# xaef_V0.net
KiCad netlist of a schematic drawn in EAGLE
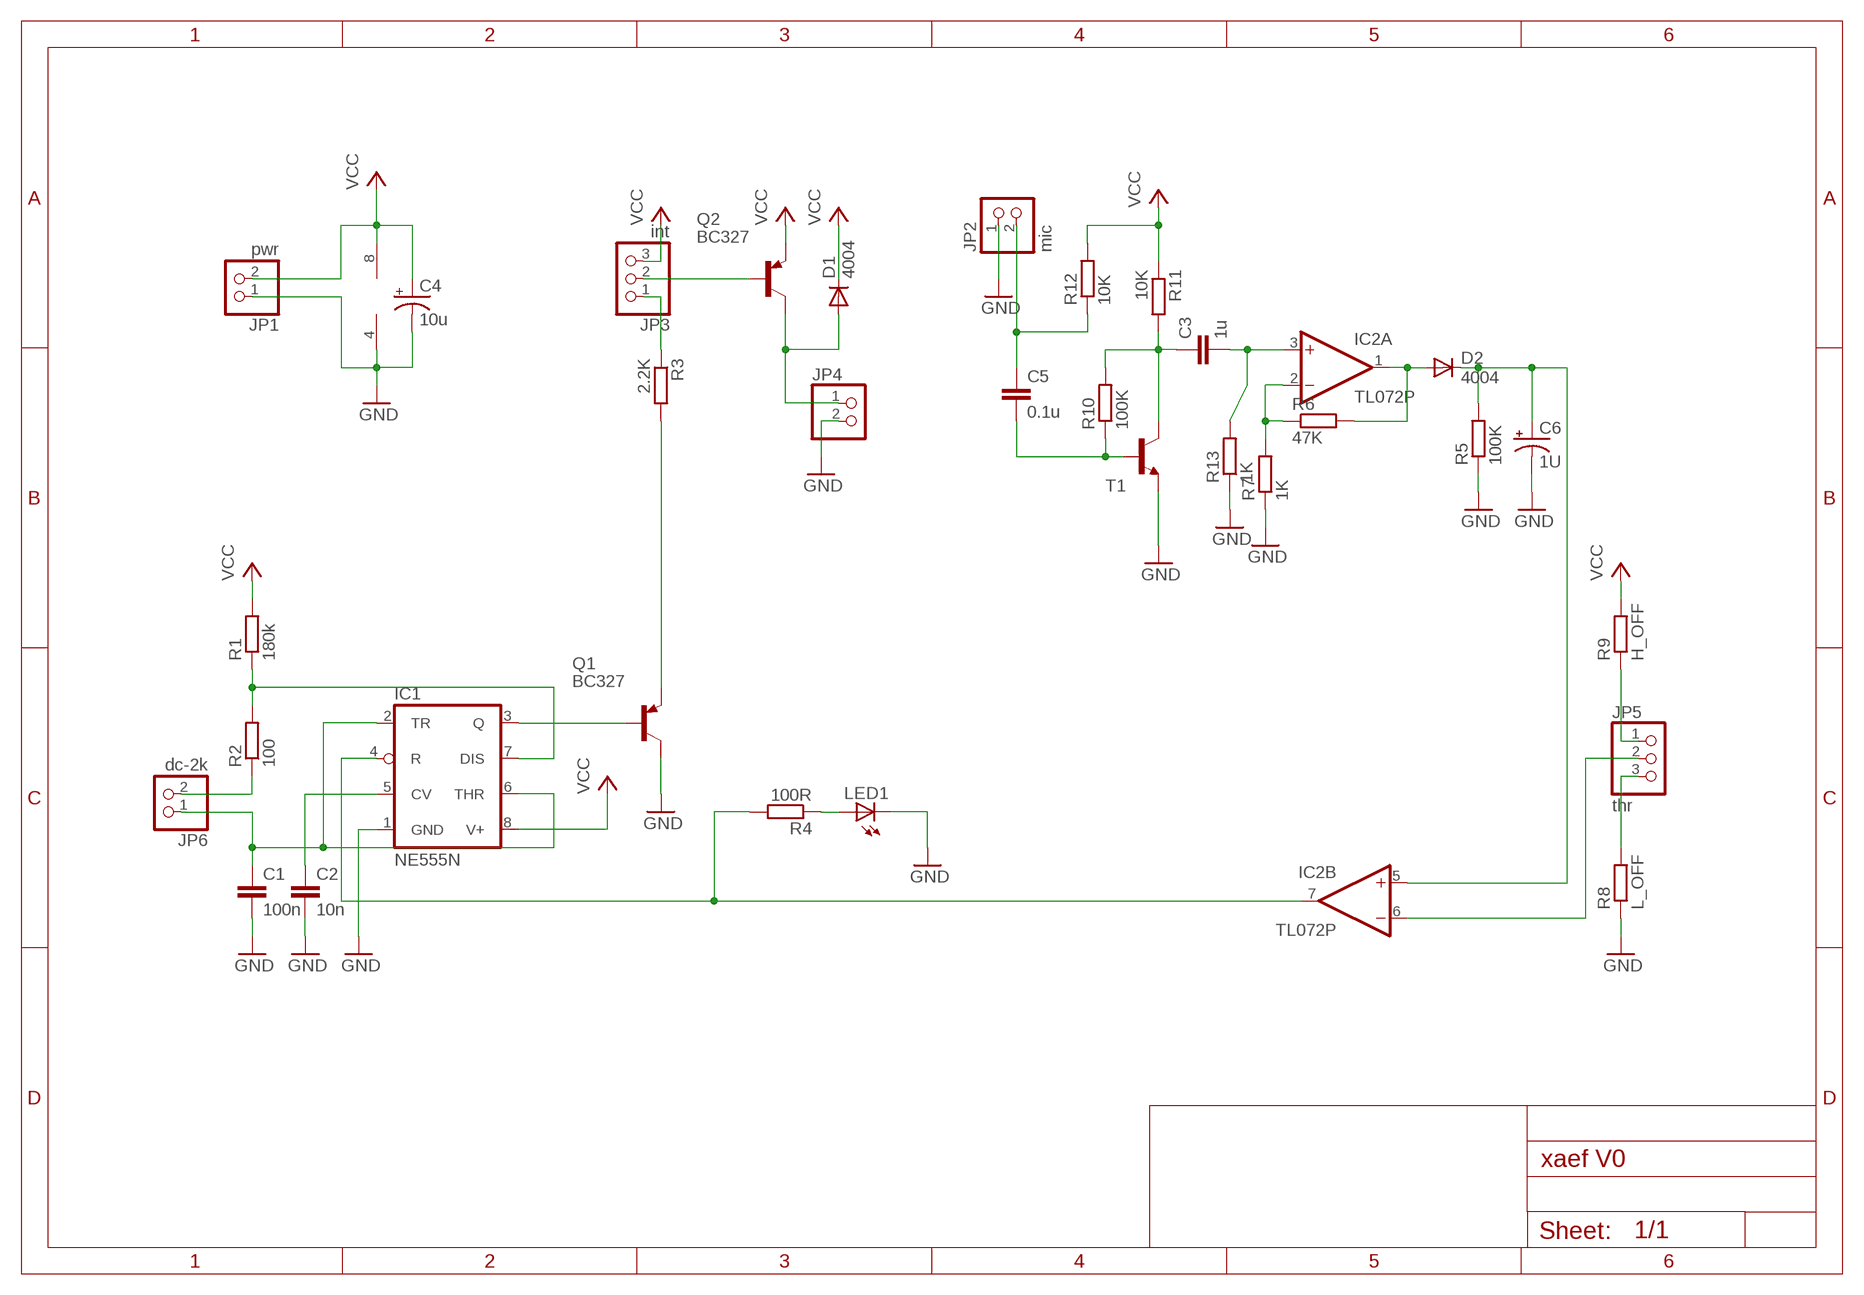
[diagram p0: schematic, sheet 1]

(export (version "E")
  (design (tool "Eeschema 10.0.6"))
  (components
    (comp (ref "C1")
      (value "100n")
      (footprint "eagle-import:C050-030X075")
      (libsource (lib "eagle-import") (part "resistor_C-EU050-030X075"))
    )
    (comp (ref "C2")
      (value "10n")
      (footprint "eagle-import:C050-030X075")
      (libsource (lib "eagle-import") (part "resistor_C-EU050-030X075"))
    )
    (comp (ref "C3")
      (value "1u")
      (footprint "eagle-import:C050-030X075")
      (libsource (lib "eagle-import") (part "resistor_C-EU050-030X075"))
    )
    (comp (ref "C4")
      (value "10u")
      (footprint "eagle-import:E3,5-8")
      (libsource (lib "eagle-import") (part "CPOL-USE3.5-8"))
    )
    (comp (ref "C5")
      (value "0.1u")
      (footprint "eagle-import:C050-025X075")
      (libsource (lib "eagle-import") (part "C-EU050-025X075"))
    )
    (comp (ref "C6")
      (value "1U")
      (footprint "eagle-import:E3,5-8")
      (libsource (lib "eagle-import") (part "CPOL-USE3.5-8"))
    )
    (comp (ref "D1")
      (value "4004")
      (footprint "eagle-import:D-2.5")
      (libsource (lib "eagle-import") (part "DIODE-D-2.5"))
    )
    (comp (ref "D2")
      (value "4004")
      (footprint "eagle-import:D-2.5")
      (libsource (lib "eagle-import") (part "DIODE-D-2.5"))
    )
    (comp (ref "IC1")
      (value "NE555N")
      (footprint "eagle-import:DIL08-ROUND")
      (libsource (lib "eagle-import") (part "555NNE"))
    )
    (comp (ref "IC2")
      (value "TL072P")
      (footprint "eagle-import:DIL08")
      (libsource (lib "eagle-import") (part "TL072P"))
    )
    (comp (ref "JP1")
      (value "pwr")
      (footprint "eagle-import:1X02")
      (libsource (lib "eagle-import") (part "PINHD-1X2"))
    )
    (comp (ref "JP2")
      (value "mic")
      (footprint "eagle-import:1X02")
      (libsource (lib "eagle-import") (part "PINHD-1X2"))
    )
    (comp (ref "JP3")
      (value "int")
      (footprint "eagle-import:1X03")
      (libsource (lib "eagle-import") (part "PINHD-1X3"))
    )
    (comp (ref "JP4")
      (value "PINHD-1X2")
      (footprint "eagle-import:1X02")
      (libsource (lib "eagle-import") (part "PINHD-1X2"))
    )
    (comp (ref "JP5")
      (value "thr")
      (footprint "eagle-import:1X03")
      (libsource (lib "eagle-import") (part "PINHD-1X3"))
    )
    (comp (ref "JP6")
      (value "dc-2k")
      (footprint "eagle-import:1X02")
      (libsource (lib "eagle-import") (part "PINHD-1X2"))
    )
    (comp (ref "LED1")
      (value "LED5MM")
      (footprint "eagle-import:LED5MM")
      (libsource (lib "eagle-import") (part "LED5MM"))
    )
    (comp (ref "Q1")
      (value "BC327")
      (footprint "eagle-import:TO92-EBC")
      (libsource (lib "eagle-import") (part "BC327-25"))
    )
    (comp (ref "Q2")
      (value "BC327")
      (footprint "eagle-import:TO92-EBC")
      (libsource (lib "eagle-import") (part "BC327-25"))
    )
    (comp (ref "R1")
      (value "180k")
      (footprint "eagle-import:0207_2V")
      (libsource (lib "eagle-import") (part "R-EU_0207/2V"))
    )
    (comp (ref "R2")
      (value "100")
      (footprint "eagle-import:0207_2V")
      (libsource (lib "eagle-import") (part "R-EU_0207/2V"))
    )
    (comp (ref "R3")
      (value "2.2K")
      (footprint "eagle-import:0207_2V")
      (libsource (lib "eagle-import") (part "R-EU_0207/2V"))
    )
    (comp (ref "R4")
      (value "100R")
      (footprint "eagle-import:0207_2V")
      (libsource (lib "eagle-import") (part "R-EU_0207/2V"))
    )
    (comp (ref "R5")
      (value "100K")
      (footprint "eagle-import:0207_2V")
      (libsource (lib "eagle-import") (part "R-EU_0207/2V"))
    )
    (comp (ref "R6")
      (value "47K")
      (footprint "eagle-import:0207_2V")
      (libsource (lib "eagle-import") (part "R-EU_0207/2V"))
    )
    (comp (ref "R7")
      (value "1K")
      (footprint "eagle-import:0207_2V")
      (libsource (lib "eagle-import") (part "R-EU_0207/2V"))
    )
    (comp (ref "R8")
      (value "L_OFF")
      (footprint "eagle-import:0207_2V")
      (libsource (lib "eagle-import") (part "R-EU_0207/2V"))
    )
    (comp (ref "R9")
      (value "H_OFF")
      (footprint "eagle-import:0207_2V")
      (libsource (lib "eagle-import") (part "R-EU_0207/2V"))
    )
    (comp (ref "R10")
      (value "100K")
      (footprint "eagle-import:0207_2V")
      (libsource (lib "eagle-import") (part "R-EU_0207/2V"))
    )
    (comp (ref "R11")
      (value "10K")
      (footprint "eagle-import:0207_2V")
      (libsource (lib "eagle-import") (part "R-EU_0207/2V"))
    )
    (comp (ref "R12")
      (value "10K")
      (footprint "eagle-import:0207_2V")
      (libsource (lib "eagle-import") (part "R-EU_0207/2V"))
    )
    (comp (ref "R13")
      (value "1K")
      (footprint "eagle-import:0207_2V")
      (libsource (lib "eagle-import") (part "R-EU_0207/2V"))
    )
    (comp (ref "T1")
      (value "2N3904-NPN-TO92-EBC")
      (footprint "eagle-import:TO92-EBC")
      (libsource (lib "eagle-import") (part "-NPN-TO92-EBC2N3904"))
    )
  )
  (nets
    (net (code "1") (name "GND") (class "Default")
      (node (ref "C1") (pin "2") (pinfunction "2_2") (pintype "passive"))
      (node (ref "C2") (pin "2") (pinfunction "2_2") (pintype "passive"))
      (node (ref "C4") (pin "-") (pinfunction "-_-") (pintype "passive"))
      (node (ref "C6") (pin "-") (pinfunction "-_-") (pintype "passive"))
      (node (ref "IC1") (pin "1") (pinfunction "GND_1") (pintype "power_in"))
      (node (ref "IC2") (pin "4") (pinfunction "V-_4") (pintype "power_in"))
      (node (ref "JP1") (pin "1") (pinfunction "1_1") (pintype "passive"))
      (node (ref "JP2") (pin "1") (pinfunction "1_1") (pintype "passive"))
      (node (ref "JP4") (pin "2") (pinfunction "2_2") (pintype "passive"))
      (node (ref "LED1") (pin "K") (pinfunction "C_K") (pintype "passive"))
      (node (ref "Q1") (pin "C") (pinfunction "C_C") (pintype "passive"))
      (node (ref "R13") (pin "1") (pinfunction "1_1") (pintype "passive"))
      (node (ref "R5") (pin "1") (pinfunction "1_1") (pintype "passive"))
      (node (ref "R7") (pin "1") (pinfunction "1_1") (pintype "passive"))
      (node (ref "R8") (pin "1") (pinfunction "1_1") (pintype "passive"))
      (node (ref "T1") (pin "E") (pinfunction "E_E") (pintype "passive"))
    )
    (net (code "2") (name "Net-(C3-Pad1)") (class "Default")
      (node (ref "C3") (pin "1") (pinfunction "1_1") (pintype "passive"))
      (node (ref "R10") (pin "2") (pinfunction "2_2") (pintype "passive"))
      (node (ref "R11") (pin "2") (pinfunction "2_2") (pintype "passive"))
      (node (ref "T1") (pin "C") (pinfunction "C_C") (pintype "passive"))
    )
    (net (code "3") (name "Net-(C5-Pad1)") (class "Default")
      (node (ref "C5") (pin "1") (pinfunction "1_1") (pintype "passive"))
      (node (ref "JP2") (pin "2") (pinfunction "2_2") (pintype "passive"))
      (node (ref "R12") (pin "1") (pinfunction "1_1") (pintype "passive"))
    )
    (net (code "4") (name "Net-(C5-Pad2)") (class "Default")
      (node (ref "C5") (pin "2") (pinfunction "2_2") (pintype "passive"))
      (node (ref "R10") (pin "1") (pinfunction "1_1") (pintype "passive"))
      (node (ref "T1") (pin "B") (pinfunction "B_B") (pintype "passive"))
    )
    (net (code "5") (name "Net-(D1-PadA)") (class "Default")
      (node (ref "D1") (pin "A") (pinfunction "A_A") (pintype "passive"))
      (node (ref "JP4") (pin "1") (pinfunction "1_1") (pintype "passive"))
      (node (ref "Q2") (pin "C") (pinfunction "C_C") (pintype "passive"))
    )
    (net (code "6") (name "Net-(IC1-CV)") (class "Default")
      (node (ref "C2") (pin "1") (pinfunction "1_1") (pintype "passive"))
      (node (ref "IC1") (pin "5") (pinfunction "CV_5") (pintype "input"))
    )
    (net (code "7") (name "Net-(IC1-DIS)") (class "Default")
      (node (ref "IC1") (pin "7") (pinfunction "DIS_7") (pintype "input"))
      (node (ref "R1") (pin "1") (pinfunction "1_1") (pintype "passive"))
      (node (ref "R2") (pin "2") (pinfunction "2_2") (pintype "passive"))
    )
    (net (code "8") (name "Net-(IC1-Q)") (class "Default")
      (node (ref "IC1") (pin "3") (pinfunction "Q_3") (pintype "output"))
      (node (ref "Q1") (pin "B") (pinfunction "B_B") (pintype "passive"))
    )
    (net (code "9") (name "Net-(IC1-R)") (class "Default")
      (node (ref "IC1") (pin "4") (pinfunction "R_4") (pintype "input"))
      (node (ref "IC2") (pin "7") (pinfunction "OUT_7") (pintype "output"))
      (node (ref "R4") (pin "2") (pinfunction "2_2") (pintype "passive"))
    )
    (net (code "10") (name "Net-(IC1-THR)") (class "Default")
      (node (ref "C1") (pin "1") (pinfunction "1_1") (pintype "passive"))
      (node (ref "IC1") (pin "2") (pinfunction "TR_2") (pintype "input"))
      (node (ref "IC1") (pin "6") (pinfunction "THR_6") (pintype "input"))
      (node (ref "JP6") (pin "1") (pinfunction "1_1") (pintype "passive"))
    )
    (net (code "11") (name "Net-(IC2A-+IN)") (class "Default")
      (node (ref "C3") (pin "2") (pinfunction "2_2") (pintype "passive"))
      (node (ref "IC2") (pin "3") (pinfunction "+IN_3") (pintype "input"))
      (node (ref "R13") (pin "2") (pinfunction "2_2") (pintype "passive"))
    )
    (net (code "12") (name "Net-(IC2A--IN)") (class "Default")
      (node (ref "IC2") (pin "2") (pinfunction "-IN_2") (pintype "input"))
      (node (ref "R6") (pin "1") (pinfunction "1_1") (pintype "passive"))
      (node (ref "R7") (pin "2") (pinfunction "2_2") (pintype "passive"))
    )
    (net (code "13") (name "Net-(IC2A-OUT)") (class "Default")
      (node (ref "D2") (pin "A") (pinfunction "A_A") (pintype "passive"))
      (node (ref "IC2") (pin "1") (pinfunction "OUT_1") (pintype "output"))
      (node (ref "R6") (pin "2") (pinfunction "2_2") (pintype "passive"))
    )
    (net (code "14") (name "Net-(IC2B-+IN)") (class "Default")
      (node (ref "C6") (pin "+") (pinfunction "+_+") (pintype "passive"))
      (node (ref "D2") (pin "C") (pinfunction "C_C") (pintype "passive"))
      (node (ref "IC2") (pin "5") (pinfunction "+IN_5") (pintype "input"))
      (node (ref "R5") (pin "2") (pinfunction "2_2") (pintype "passive"))
    )
    (net (code "15") (name "Net-(IC2B--IN)") (class "Default")
      (node (ref "IC2") (pin "6") (pinfunction "-IN_6") (pintype "input"))
      (node (ref "JP5") (pin "2") (pinfunction "2_2") (pintype "passive"))
    )
    (net (code "16") (name "Net-(JP3-Pad1)") (class "Default")
      (node (ref "JP3") (pin "1") (pinfunction "1_1") (pintype "passive"))
      (node (ref "R3") (pin "1") (pinfunction "1_1") (pintype "passive"))
    )
    (net (code "17") (name "Net-(JP3-Pad2)") (class "Default")
      (node (ref "JP3") (pin "2") (pinfunction "2_2") (pintype "passive"))
      (node (ref "Q2") (pin "B") (pinfunction "B_B") (pintype "passive"))
    )
    (net (code "18") (name "Net-(JP5-Pad1)") (class "Default")
      (node (ref "JP5") (pin "1") (pinfunction "1_1") (pintype "passive"))
      (node (ref "R9") (pin "1") (pinfunction "1_1") (pintype "passive"))
    )
    (net (code "19") (name "Net-(JP5-Pad3)") (class "Default")
      (node (ref "JP5") (pin "3") (pinfunction "3_3") (pintype "passive"))
      (node (ref "R8") (pin "2") (pinfunction "2_2") (pintype "passive"))
    )
    (net (code "20") (name "Net-(JP6-Pad2)") (class "Default")
      (node (ref "JP6") (pin "2") (pinfunction "2_2") (pintype "passive"))
      (node (ref "R2") (pin "1") (pinfunction "1_1") (pintype "passive"))
    )
    (net (code "21") (name "Net-(LED1-PadA)") (class "Default")
      (node (ref "LED1") (pin "A") (pinfunction "A_A") (pintype "passive"))
      (node (ref "R4") (pin "1") (pinfunction "1_1") (pintype "passive"))
    )
    (net (code "22") (name "Net-(Q1-PadE)") (class "Default")
      (node (ref "Q1") (pin "E") (pinfunction "E_E") (pintype "passive"))
      (node (ref "R3") (pin "2") (pinfunction "2_2") (pintype "passive"))
    )
    (net (code "23") (name "VCC") (class "Default")
      (node (ref "C4") (pin "+") (pinfunction "+_+") (pintype "passive"))
      (node (ref "D1") (pin "C") (pinfunction "C_C") (pintype "passive"))
      (node (ref "IC1") (pin "8") (pinfunction "V+_8") (pintype "power_in"))
      (node (ref "IC2") (pin "8") (pinfunction "V+_8") (pintype "power_in"))
      (node (ref "JP1") (pin "2") (pinfunction "2_2") (pintype "passive"))
      (node (ref "JP3") (pin "3") (pinfunction "3_3") (pintype "passive"))
      (node (ref "Q2") (pin "E") (pinfunction "E_E") (pintype "passive"))
      (node (ref "R1") (pin "2") (pinfunction "2_2") (pintype "passive"))
      (node (ref "R11") (pin "1") (pinfunction "1_1") (pintype "passive"))
      (node (ref "R12") (pin "2") (pinfunction "2_2") (pintype "passive"))
      (node (ref "R9") (pin "2") (pinfunction "2_2") (pintype "passive"))
    )
  )
)
